# MKXdbV2_DAC0.net
KiCad netlist of a schematic drawn in Altium Designer
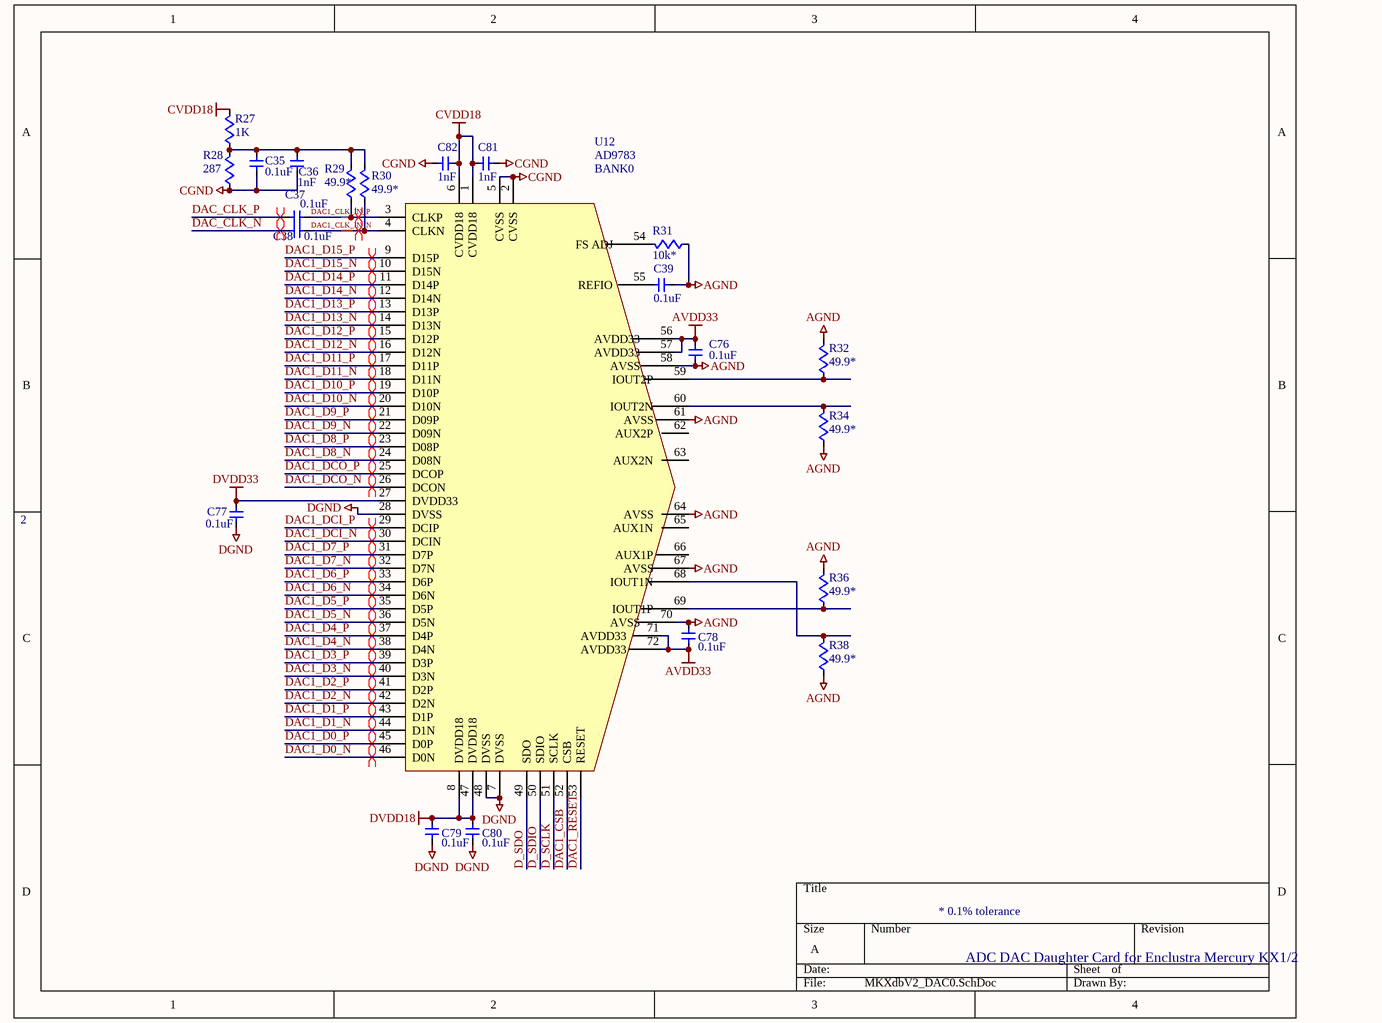
[diagram p0: MKXdbV2_DAC0.SchDoc]

(export (version "E")
  (design (tool "Eeschema 10.0.6"))
  (components
    (comp (ref "C35")
      (value "0.1uF")
      (footprint "0603w")
      (description "capacitor")
      (fields
        (field (name "MANUFACTURER") "Kemet")
        (field (name "MANUFACTURER PART NUMBER") "C0603C104K3RACTU")
      )
      (libsource (lib "KX1_DB") (part "CAP_SM_1"))
    )
    (comp (ref "C36")
      (value "1nF")
      (footprint "0603w")
      (description "capacitor")
      (fields
        (field (name "MANUFACTURER") "Murata Electronics North America")
        (field (name "MANUFACTURER PART NUMBER") "GRM188R71H102KA01D")
      )
      (libsource (lib "KX1_DB") (part "CAP_SM_1"))
    )
    (comp (ref "C37")
      (value "0.1uF")
      (footprint "1206")
      (description "capacitor")
      (fields
        (field (name "MANUFACTURER") "Murata Electronics North America")
        (field (name "MANUFACTURER PART NUMBER") "GRM31C5C1E104JA01L")
      )
      (libsource (lib "KX1_DB") (part "CAP_SM_1"))
    )
    (comp (ref "C38")
      (value "0.1uF")
      (footprint "1206")
      (description "capacitor")
      (fields
        (field (name "MANUFACTURER") "Murata Electronics North America")
        (field (name "MANUFACTURER PART NUMBER") "GRM31C5C1E104JA01L")
      )
      (libsource (lib "KX1_DB") (part "CAP_SM_1"))
    )
    (comp (ref "C39")
      (value "0.1uF")
      (footprint "0603w")
      (description "capacitor")
      (fields
        (field (name "MANUFACTURER") "Kemet")
        (field (name "MANUFACTURER PART NUMBER") "C0603C104K3RACTU")
      )
      (libsource (lib "KX1_DB") (part "CAP_SM_1"))
    )
    (comp (ref "C76")
      (value "0.1uF")
      (footprint "0603w")
      (description "capacitor")
      (fields
        (field (name "MANUFACTURER") "Kemet")
        (field (name "MANUFACTURER PART NUMBER") "C0603C104K3RACTU")
      )
      (libsource (lib "KX1_DB") (part "CAP_SM_1"))
    )
    (comp (ref "C77")
      (value "0.1uF")
      (footprint "0603w")
      (description "capacitor")
      (fields
        (field (name "MANUFACTURER") "Kemet")
        (field (name "MANUFACTURER PART NUMBER") "C0603C104K3RACTU")
      )
      (libsource (lib "KX1_DB") (part "CAP_SM_1"))
    )
    (comp (ref "C78")
      (value "0.1uF")
      (footprint "0603w")
      (description "capacitor")
      (fields
        (field (name "MANUFACTURER") "Kemet")
        (field (name "MANUFACTURER PART NUMBER") "C0603C104K3RACTU")
      )
      (libsource (lib "KX1_DB") (part "CAP_SM_1"))
    )
    (comp (ref "C79")
      (value "0.1uF")
      (footprint "0603w")
      (description "capacitor")
      (fields
        (field (name "MANUFACTURER") "Kemet")
        (field (name "MANUFACTURER PART NUMBER") "C0603C104K3RACTU")
      )
      (libsource (lib "KX1_DB") (part "CAP_SM_1"))
    )
    (comp (ref "C80")
      (value "0.1uF")
      (footprint "0603w")
      (description "capacitor")
      (fields
        (field (name "MANUFACTURER") "Kemet")
        (field (name "MANUFACTURER PART NUMBER") "C0603C104K3RACTU")
      )
      (libsource (lib "KX1_DB") (part "CAP_SM_1"))
    )
    (comp (ref "C81")
      (value "1nF")
      (footprint "0603w")
      (description "capacitor")
      (fields
        (field (name "MANUFACTURER") "Murata Electronics North America")
        (field (name "MANUFACTURER PART NUMBER") "GRM188R71H102KA01D")
      )
      (libsource (lib "KX1_DB") (part "CAP_SM_1"))
    )
    (comp (ref "C82")
      (value "1nF")
      (footprint "0603w")
      (description "capacitor")
      (fields
        (field (name "MANUFACTURER") "Murata Electronics North America")
        (field (name "MANUFACTURER PART NUMBER") "GRM188R71H102KA01D")
      )
      (libsource (lib "KX1_DB") (part "CAP_SM_1"))
    )
    (comp (ref "R27")
      (value "1K")
      (footprint "0603w")
      (description "resistor")
      (fields
        (field (name "MANUFACTURER") "Yageo")
        (field (name "MANUFACTURER PART NUMBER") "RC0603FR-071KL")
      )
      (libsource (lib "KX1_DB") (part "RES_SM"))
    )
    (comp (ref "R28")
      (value "287")
      (footprint "0603w")
      (description "resistor")
      (fields
        (field (name "MANUFACTURER") "Yageo")
        (field (name "MANUFACTURER PART NUMBER") "RC0603FR-07287RL")
      )
      (libsource (lib "KX1_DB") (part "RES_SM"))
    )
    (comp (ref "R29")
      (value "49.9*")
      (footprint "0603w")
      (description "resistor")
      (fields
        (field (name "MANUFACTURER") "Stackpole Electronics Inc")
        (field (name "MANUFACTURER PART NUMBER") "RNCS0603BKE49R9")
      )
      (libsource (lib "KX1_DB") (part "RES_SM"))
    )
    (comp (ref "R30")
      (value "49.9*")
      (footprint "0603w")
      (description "resistor")
      (fields
        (field (name "MANUFACTURER") "Stackpole Electronics Inc")
        (field (name "MANUFACTURER PART NUMBER") "RNCS0603BKE49R9")
      )
      (libsource (lib "KX1_DB") (part "RES_SM"))
    )
    (comp (ref "R31")
      (value "10k*")
      (footprint "0603w")
      (description "resistor")
      (fields
        (field (name "MANUFACTURER") "Susumu")
        (field (name "MANUFACTURER PART NUMBER") "RG1608P-103-B-T5")
      )
      (libsource (lib "KX1_DB") (part "RES_SM"))
    )
    (comp (ref "R32")
      (value "49.9*")
      (footprint "0603w")
      (description "resistor")
      (fields
        (field (name "MANUFACTURER") "Stackpole Electronics Inc")
        (field (name "MANUFACTURER PART NUMBER") "RNCS0603BKE49R9")
      )
      (libsource (lib "KX1_DB") (part "RES_SM"))
    )
    (comp (ref "R34")
      (value "49.9*")
      (footprint "0603w")
      (description "resistor")
      (fields
        (field (name "MANUFACTURER") "Stackpole Electronics Inc")
        (field (name "MANUFACTURER PART NUMBER") "RNCS0603BKE49R9")
      )
      (libsource (lib "KX1_DB") (part "RES_SM"))
    )
    (comp (ref "R36")
      (value "49.9*")
      (footprint "0603w")
      (description "resistor")
      (fields
        (field (name "MANUFACTURER") "Stackpole Electronics Inc")
        (field (name "MANUFACTURER PART NUMBER") "RNCS0603BKE49R9")
      )
      (libsource (lib "KX1_DB") (part "RES_SM"))
    )
    (comp (ref "R38")
      (value "49.9*")
      (footprint "0603w")
      (description "resistor")
      (fields
        (field (name "MANUFACTURER") "Stackpole Electronics Inc")
        (field (name "MANUFACTURER PART NUMBER") "RNCS0603BKE49R9")
      )
      (libsource (lib "KX1_DB") (part "RES_SM"))
    )
    (comp (ref "U12")
      (value "AD9783")
      (footprint "LFCSP72")
      (description "DAC LVDS DUAL16BIT 500MSPS")
      (libsource (lib "KX1_DB") (part "AD9783"))
    )
  )
  (nets
    (net (code "1") (name "/DAC1_CLK_IN_N") (class "Default")
      (node (ref "C38") (pin "2") (pintype "passive"))
      (node (ref "R30") (pin "1") (pintype "passive"))
      (node (ref "U12") (pin "4") (pinfunction "CLKN_4") (pintype "passive"))
    )
    (net (code "2") (name "/DAC1_CLK_IN_P") (class "Default")
      (node (ref "C37") (pin "2") (pintype "passive"))
      (node (ref "R29") (pin "1") (pintype "passive"))
      (node (ref "U12") (pin "3") (pinfunction "CLKP_3") (pintype "passive"))
    )
    (net (code "3") (name "/DAC1_CSB") (class "Default")
      (node (ref "U12") (pin "52") (pinfunction "CSB_52") (pintype "passive"))
    )
    (net (code "4") (name "/DAC1_D0_N") (class "Default")
      (node (ref "U12") (pin "46") (pinfunction "D0N_46") (pintype "passive"))
    )
    (net (code "5") (name "/DAC1_D0_P") (class "Default")
      (node (ref "U12") (pin "45") (pinfunction "D0P_45") (pintype "passive"))
    )
    (net (code "6") (name "/DAC1_D1_N") (class "Default")
      (node (ref "U12") (pin "44") (pinfunction "D1N_44") (pintype "passive"))
    )
    (net (code "7") (name "/DAC1_D1_P") (class "Default")
      (node (ref "U12") (pin "43") (pinfunction "D1P_43") (pintype "passive"))
    )
    (net (code "8") (name "/DAC1_D2_N") (class "Default")
      (node (ref "U12") (pin "42") (pinfunction "D2N_42") (pintype "passive"))
    )
    (net (code "9") (name "/DAC1_D2_P") (class "Default")
      (node (ref "U12") (pin "41") (pinfunction "D2P_41") (pintype "passive"))
    )
    (net (code "10") (name "/DAC1_D3_N") (class "Default")
      (node (ref "U12") (pin "40") (pinfunction "D3N_40") (pintype "passive"))
    )
    (net (code "11") (name "/DAC1_D3_P") (class "Default")
      (node (ref "U12") (pin "39") (pinfunction "D3P_39") (pintype "passive"))
    )
    (net (code "12") (name "/DAC1_D4_N") (class "Default")
      (node (ref "U12") (pin "38") (pinfunction "D4N_38") (pintype "passive"))
    )
    (net (code "13") (name "/DAC1_D4_P") (class "Default")
      (node (ref "U12") (pin "37") (pinfunction "D4P_37") (pintype "passive"))
    )
    (net (code "14") (name "/DAC1_D5_N") (class "Default")
      (node (ref "U12") (pin "36") (pinfunction "D5N_36") (pintype "passive"))
    )
    (net (code "15") (name "/DAC1_D5_P") (class "Default")
      (node (ref "U12") (pin "35") (pinfunction "D5P_35") (pintype "passive"))
    )
    (net (code "16") (name "/DAC1_D6_N") (class "Default")
      (node (ref "U12") (pin "34") (pinfunction "D6N_34") (pintype "passive"))
    )
    (net (code "17") (name "/DAC1_D6_P") (class "Default")
      (node (ref "U12") (pin "33") (pinfunction "D6P_33") (pintype "passive"))
    )
    (net (code "18") (name "/DAC1_D7_N") (class "Default")
      (node (ref "U12") (pin "32") (pinfunction "D7N_32") (pintype "passive"))
    )
    (net (code "19") (name "/DAC1_D7_P") (class "Default")
      (node (ref "U12") (pin "31") (pinfunction "D7P_31") (pintype "passive"))
    )
    (net (code "20") (name "/DAC1_D8_N") (class "Default")
      (node (ref "U12") (pin "24") (pinfunction "D08N_24") (pintype "passive"))
    )
    (net (code "21") (name "/DAC1_D8_P") (class "Default")
      (node (ref "U12") (pin "23") (pinfunction "D08P_23") (pintype "passive"))
    )
    (net (code "22") (name "/DAC1_D9_N") (class "Default")
      (node (ref "U12") (pin "22") (pinfunction "D09N_22") (pintype "passive"))
    )
    (net (code "23") (name "/DAC1_D9_P") (class "Default")
      (node (ref "U12") (pin "21") (pinfunction "D09P_21") (pintype "passive"))
    )
    (net (code "24") (name "/DAC1_D10_N") (class "Default")
      (node (ref "U12") (pin "20") (pinfunction "D10N_20") (pintype "passive"))
    )
    (net (code "25") (name "/DAC1_D10_P") (class "Default")
      (node (ref "U12") (pin "19") (pinfunction "D10P_19") (pintype "passive"))
    )
    (net (code "26") (name "/DAC1_D11_N") (class "Default")
      (node (ref "U12") (pin "18") (pinfunction "D11N_18") (pintype "passive"))
    )
    (net (code "27") (name "/DAC1_D11_P") (class "Default")
      (node (ref "U12") (pin "17") (pinfunction "D11P_17") (pintype "passive"))
    )
    (net (code "28") (name "/DAC1_D12_N") (class "Default")
      (node (ref "U12") (pin "16") (pinfunction "D12N_16") (pintype "passive"))
    )
    (net (code "29") (name "/DAC1_D12_P") (class "Default")
      (node (ref "U12") (pin "15") (pinfunction "D12P_15") (pintype "passive"))
    )
    (net (code "30") (name "/DAC1_D13_N") (class "Default")
      (node (ref "U12") (pin "14") (pinfunction "D13N_14") (pintype "passive"))
    )
    (net (code "31") (name "/DAC1_D13_P") (class "Default")
      (node (ref "U12") (pin "13") (pinfunction "D13P_13") (pintype "passive"))
    )
    (net (code "32") (name "/DAC1_D14_N") (class "Default")
      (node (ref "U12") (pin "12") (pinfunction "D14N_12") (pintype "passive"))
    )
    (net (code "33") (name "/DAC1_D14_P") (class "Default")
      (node (ref "U12") (pin "11") (pinfunction "D14P_11") (pintype "passive"))
    )
    (net (code "34") (name "/DAC1_D15_N") (class "Default")
      (node (ref "U12") (pin "10") (pinfunction "D15N_10") (pintype "passive"))
    )
    (net (code "35") (name "/DAC1_D15_P") (class "Default")
      (node (ref "U12") (pin "9") (pinfunction "D15P_9") (pintype "passive"))
    )
    (net (code "36") (name "/DAC1_DCI_N") (class "Default")
      (node (ref "U12") (pin "30") (pinfunction "DCIN_30") (pintype "passive"))
    )
    (net (code "37") (name "/DAC1_DCI_P") (class "Default")
      (node (ref "U12") (pin "29") (pinfunction "DCIP_29") (pintype "passive"))
    )
    (net (code "38") (name "/DAC1_DCO_N") (class "Default")
      (node (ref "U12") (pin "26") (pinfunction "DCON_26") (pintype "passive"))
    )
    (net (code "39") (name "/DAC1_DCO_P") (class "Default")
      (node (ref "U12") (pin "25") (pinfunction "DCOP_25") (pintype "passive"))
    )
    (net (code "40") (name "/DAC1_RESET") (class "Default")
      (node (ref "U12") (pin "53") (pinfunction "RESET_53") (pintype "passive"))
    )
    (net (code "41") (name "/DAC_CLK_N") (class "Default") (node (ref "C38") (pin "1") (pintype "passive")))
    (net (code "42") (name "/DAC_CLK_P") (class "Default") (node (ref "C37") (pin "1") (pintype "passive")))
    (net (code "43") (name "/D_SCLK") (class "Default")
      (node (ref "U12") (pin "51") (pinfunction "SCLK_51") (pintype "passive"))
    )
    (net (code "44") (name "/D_SDIO") (class "Default")
      (node (ref "U12") (pin "50") (pinfunction "SDIO_50") (pintype "passive"))
    )
    (net (code "45") (name "/D_SDO") (class "Default")
      (node (ref "U12") (pin "49") (pinfunction "SDO_49") (pintype "passive"))
    )
    (net (code "46") (name "AGND") (class "Default")
      (node (ref "C39") (pin "2") (pintype "passive"))
      (node (ref "C76") (pin "1") (pintype "passive"))
      (node (ref "C78") (pin "2") (pintype "passive"))
      (node (ref "R31") (pin "1") (pintype "passive"))
      (node (ref "R32") (pin "2") (pintype "passive"))
      (node (ref "R34") (pin "1") (pintype "passive"))
      (node (ref "R36") (pin "2") (pintype "passive"))
      (node (ref "R38") (pin "1") (pintype "passive"))
      (node (ref "U12") (pin "58") (pinfunction "AVSS_58") (pintype "passive"))
      (node (ref "U12") (pin "61") (pinfunction "AVSS_61") (pintype "passive"))
      (node (ref "U12") (pin "64") (pinfunction "AVSS_64") (pintype "passive"))
      (node (ref "U12") (pin "67") (pinfunction "AVSS_67") (pintype "passive"))
      (node (ref "U12") (pin "70") (pinfunction "AVSS_70") (pintype "passive"))
    )
    (net (code "47") (name "AVDD33") (class "Default")
      (node (ref "C76") (pin "2") (pintype "passive"))
      (node (ref "C78") (pin "1") (pintype "passive"))
      (node (ref "U12") (pin "56") (pinfunction "AVDD33_56") (pintype "passive"))
      (node (ref "U12") (pin "57") (pinfunction "AVDD33_57") (pintype "passive"))
      (node (ref "U12") (pin "71") (pinfunction "AVDD33_71") (pintype "passive"))
      (node (ref "U12") (pin "72") (pinfunction "AVDD33_72") (pintype "passive"))
    )
    (net (code "48") (name "CGND") (class "Default")
      (node (ref "C35") (pin "2") (pintype "passive"))
      (node (ref "C36") (pin "2") (pintype "passive"))
      (node (ref "C81") (pin "2") (pintype "passive"))
      (node (ref "C82") (pin "2") (pintype "passive"))
      (node (ref "R28") (pin "1") (pintype "passive"))
      (node (ref "U12") (pin "2") (pinfunction "CVSS_2") (pintype "passive"))
      (node (ref "U12") (pin "5") (pinfunction "CVSS_5") (pintype "passive"))
    )
    (net (code "49") (name "CVDD18") (class "Default")
      (node (ref "C81") (pin "1") (pintype "passive"))
      (node (ref "C82") (pin "1") (pintype "passive"))
      (node (ref "R27") (pin "2") (pintype "passive"))
      (node (ref "U12") (pin "1") (pinfunction "CVDD18_1") (pintype "passive"))
      (node (ref "U12") (pin "6") (pinfunction "CVDD18_6") (pintype "passive"))
    )
    (net (code "50") (name "DGND") (class "Default")
      (node (ref "C77") (pin "2") (pintype "passive"))
      (node (ref "C79") (pin "1") (pintype "passive"))
      (node (ref "C80") (pin "1") (pintype "passive"))
      (node (ref "U12") (pin "28") (pinfunction "DVSS_28") (pintype "passive"))
      (node (ref "U12") (pin "48") (pinfunction "DVSS_48") (pintype "passive"))
      (node (ref "U12") (pin "7") (pinfunction "DVSS_7") (pintype "passive"))
    )
    (net (code "51") (name "DVDD18") (class "Default")
      (node (ref "C79") (pin "2") (pintype "passive"))
      (node (ref "C80") (pin "2") (pintype "passive"))
      (node (ref "U12") (pin "47") (pinfunction "DVDD18_47") (pintype "passive"))
      (node (ref "U12") (pin "8") (pinfunction "DVDD18_8") (pintype "passive"))
    )
    (net (code "52") (name "DVDD33") (class "Default")
      (node (ref "C77") (pin "1") (pintype "passive"))
      (node (ref "U12") (pin "27") (pinfunction "DVDD33_27") (pintype "passive"))
    )
    (net (code "53") (name "Net-(C35-Pad1)") (class "Default")
      (node (ref "C35") (pin "1") (pintype "passive"))
      (node (ref "C36") (pin "1") (pintype "passive"))
      (node (ref "R27") (pin "1") (pintype "passive"))
      (node (ref "R28") (pin "2") (pintype "passive"))
      (node (ref "R29") (pin "2") (pintype "passive"))
      (node (ref "R30") (pin "2") (pintype "passive"))
    )
    (net (code "54") (name "Net-(U12-FS_ADJ)") (class "Default")
      (node (ref "R31") (pin "2") (pintype "passive"))
      (node (ref "U12") (pin "54") (pinfunction "FS_ADJ_54") (pintype "passive"))
    )
    (net (code "55") (name "Net-(U12-IOUT1N)") (class "Default")
      (node (ref "R38") (pin "2") (pintype "passive"))
      (node (ref "U12") (pin "68") (pinfunction "IOUT1N_68") (pintype "passive"))
    )
    (net (code "56") (name "Net-(U12-IOUT1P)") (class "Default")
      (node (ref "R36") (pin "1") (pintype "passive"))
      (node (ref "U12") (pin "69") (pinfunction "IOUT1P_69") (pintype "passive"))
    )
    (net (code "57") (name "Net-(U12-IOUT2N)") (class "Default")
      (node (ref "R34") (pin "2") (pintype "passive"))
      (node (ref "U12") (pin "60") (pinfunction "IOUT2N_60") (pintype "passive"))
    )
    (net (code "58") (name "Net-(U12-IOUT2P)") (class "Default")
      (node (ref "R32") (pin "1") (pintype "passive"))
      (node (ref "U12") (pin "59") (pinfunction "IOUT2P_59") (pintype "passive"))
    )
    (net (code "59") (name "Net-(U12-REFIO)") (class "Default")
      (node (ref "C39") (pin "1") (pintype "passive"))
      (node (ref "U12") (pin "55") (pinfunction "REFIO_55") (pintype "passive"))
    )
    (net (code "60") (name "unconnected-(U12-AUX1N-Pad65)") (class "Default")
      (node (ref "U12") (pin "65") (pinfunction "AUX1N_65") (pintype "passive"))
    )
    (net (code "61") (name "unconnected-(U12-AUX1P-Pad66)") (class "Default")
      (node (ref "U12") (pin "66") (pinfunction "AUX1P_66") (pintype "passive"))
    )
    (net (code "62") (name "unconnected-(U12-AUX2N-Pad63)") (class "Default")
      (node (ref "U12") (pin "63") (pinfunction "AUX2N_63") (pintype "passive"))
    )
    (net (code "63") (name "unconnected-(U12-AUX2P-Pad62)") (class "Default")
      (node (ref "U12") (pin "62") (pinfunction "AUX2P_62") (pintype "passive"))
    )
  )
)
